# 1-Schematic_Dot_PCB_-_Dash.net
KiCad netlist of a schematic drawn in EasyEDA
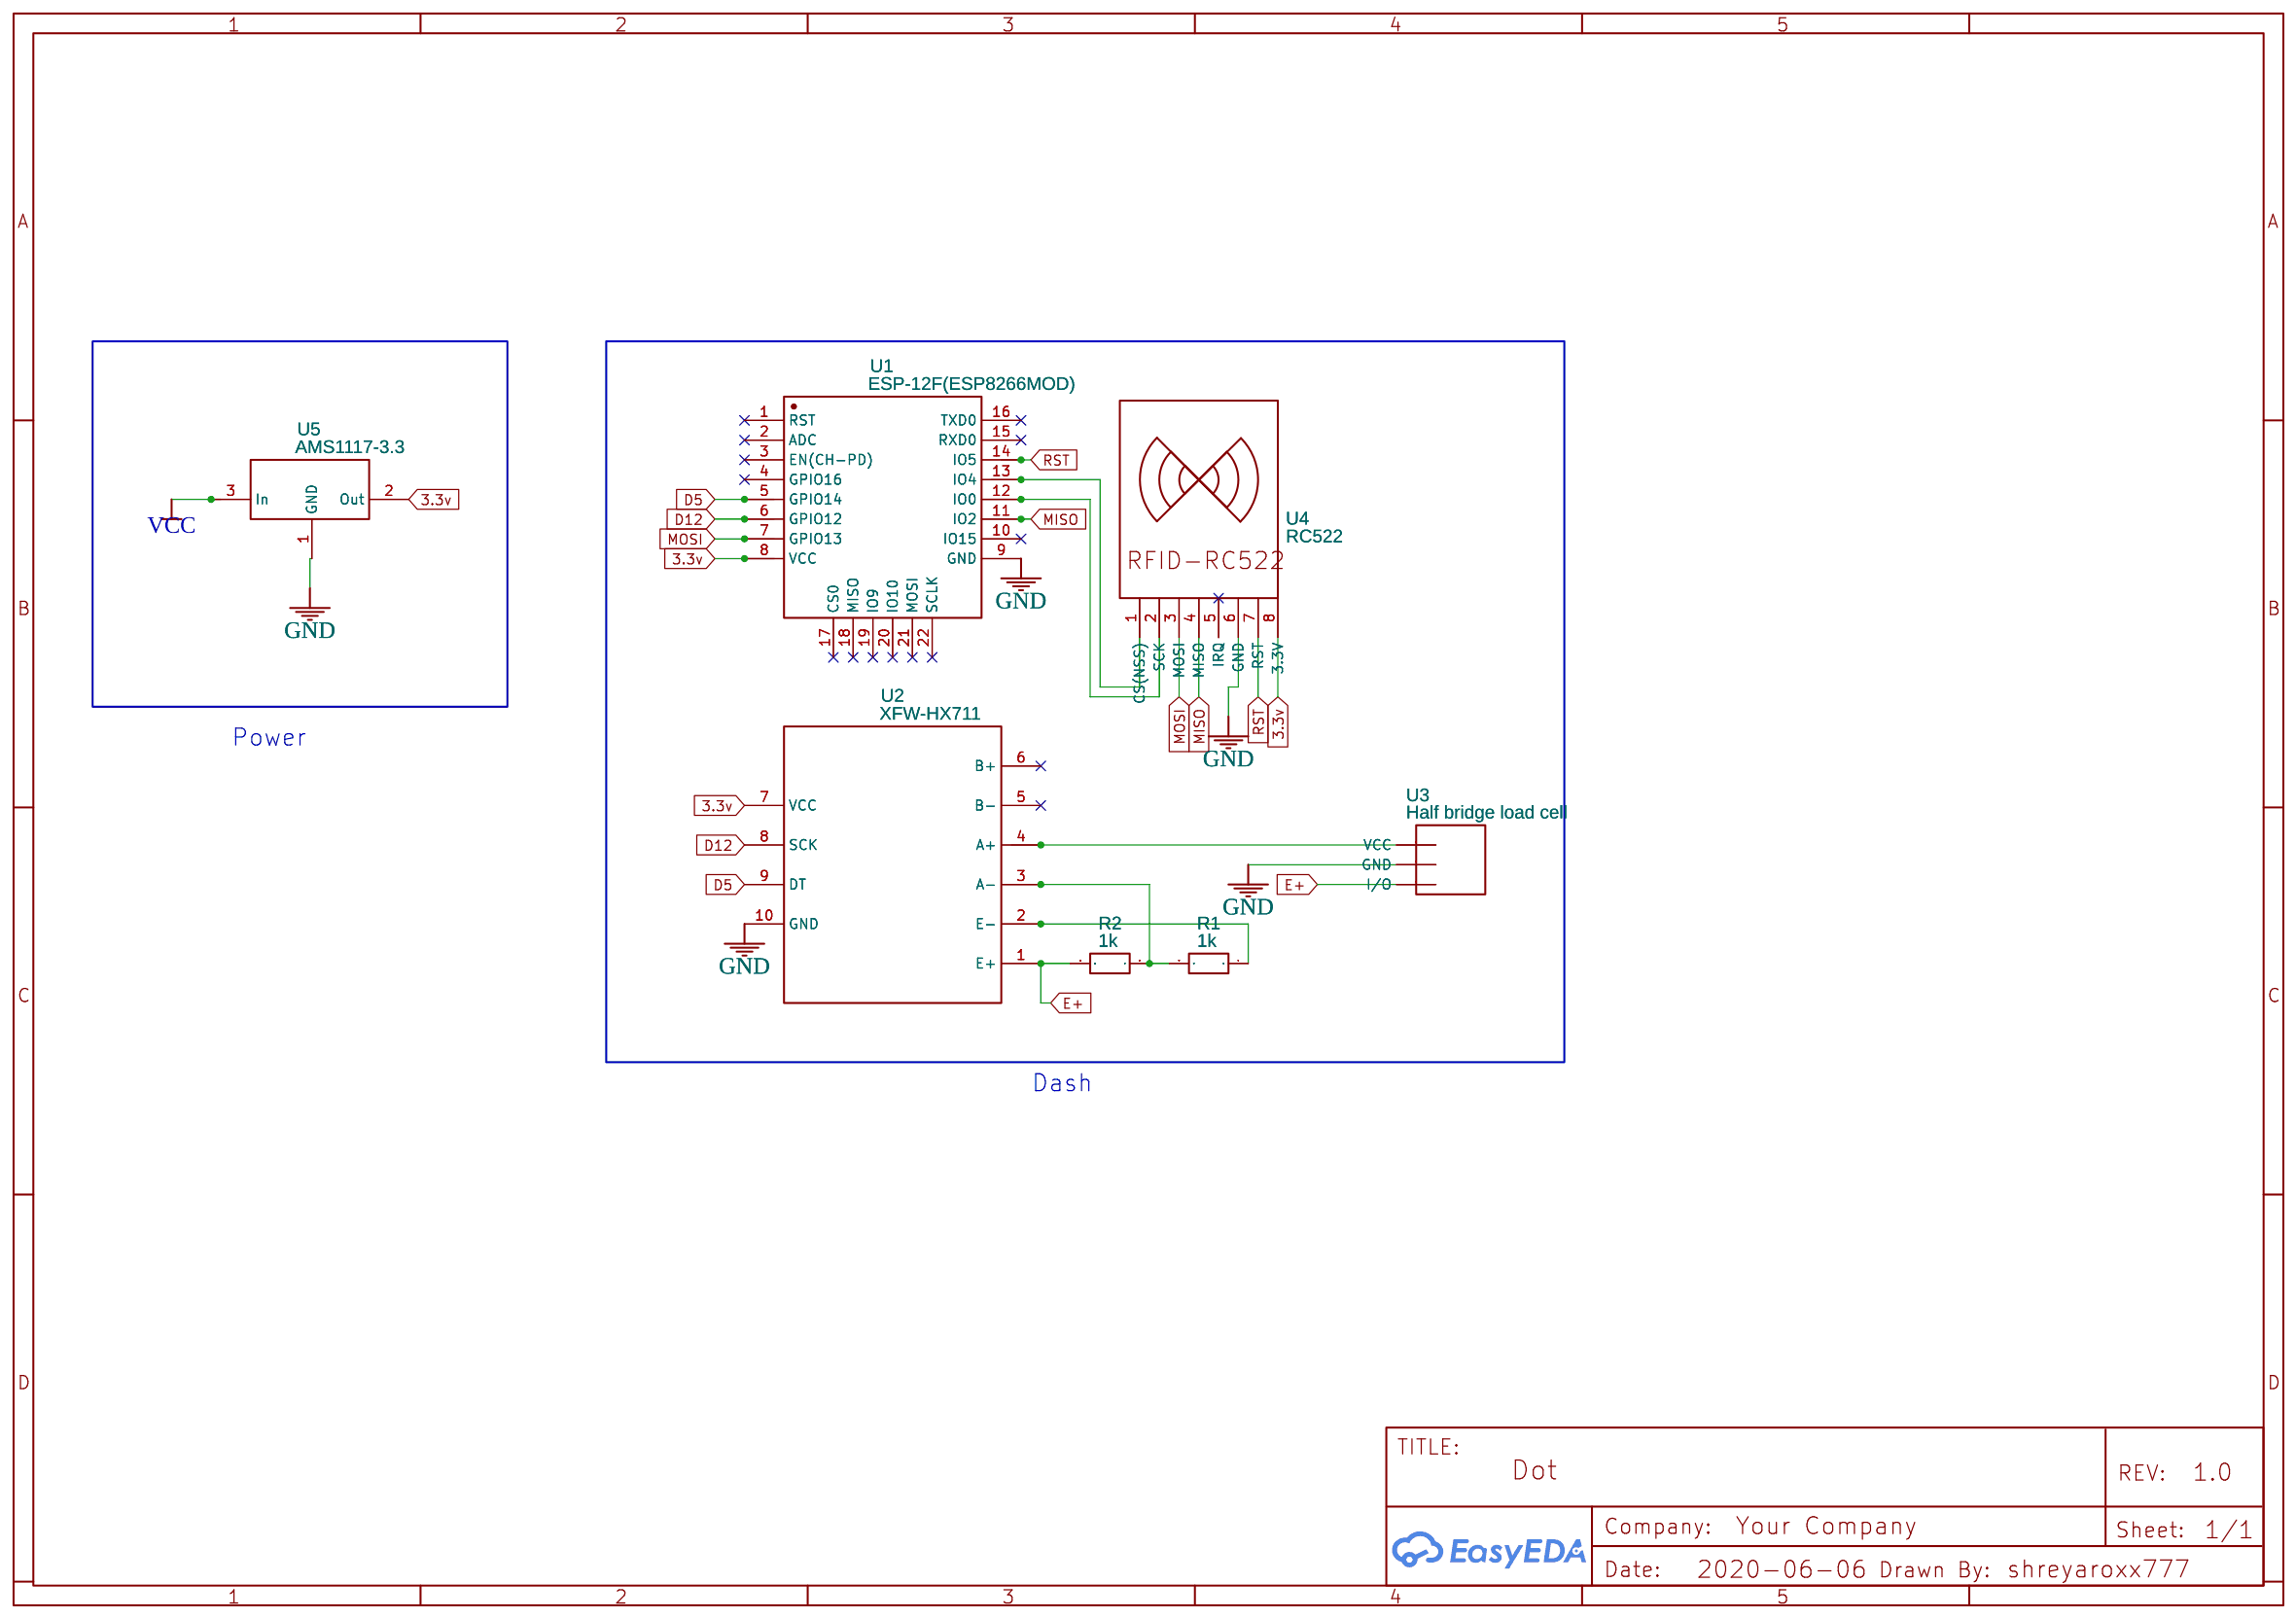
[diagram p0: schematic sheet]

(export (version "E")
  (design (tool "Eeschema 10.0.6"))
  (components
    (comp (ref "R1") (value "1k") (libsource (lib "") (part "R_0201_EU")))
    (comp (ref "R2") (value "1k") (libsource (lib "") (part "R_0201_EU")))
    (comp (ref "U1")
      (value "ESP-12F(ESP8266MOD)")
      (fields (field (name "BOM_Supplier Part") "C82891"))
      (libsource (lib "") (part "ESP-12F(ESP8266MOD)"))
    )
    (comp (ref "U2") (value "XFW-HX711") (libsource (lib "") (part "XFW-HX711")))
    (comp (ref "U3") (value "Half bridge load cell") (libsource (lib "") (part "Half bridge load cell")))
    (comp (ref "U4") (value "RC522") (libsource (lib "") (part "RC522")))
    (comp (ref "U5")
      (value "AMS1117-3.3")
      (fields (field (name "BOM_Supplier Part") "C6186"))
      (libsource (lib "") (part "AMS1117-3.3"))
    )
  )
  (nets
    (net (code "1") (name "3.3v") (class "Default")
      (node (ref "U1") (pin "8") (pinfunction "VCC_8") (pintype "unspecified"))
      (node (ref "U2") (pin "7") (pinfunction "VCC_7") (pintype "unspecified"))
      (node (ref "U4") (pin "8") (pinfunction "3.3V_8") (pintype "unspecified"))
      (node (ref "U5") (pin "2") (pinfunction "Out_2") (pintype "unspecified"))
    )
    (net (code "2") (name "D5") (class "Default")
      (node (ref "U1") (pin "5") (pinfunction "GPIO14_5") (pintype "unspecified"))
      (node (ref "U2") (pin "9") (pinfunction "DT_9") (pintype "unspecified"))
    )
    (net (code "3") (name "D12") (class "Default")
      (node (ref "U1") (pin "6") (pinfunction "GPIO12_6") (pintype "unspecified"))
      (node (ref "U2") (pin "8") (pinfunction "SCK_8") (pintype "unspecified"))
    )
    (net (code "4") (name "E+") (class "Default")
      (node (ref "R2") (pin "2") (pinfunction "2_2") (pintype "unspecified"))
      (node (ref "U2") (pin "1") (pinfunction "E+_1") (pintype "unspecified"))
      (node (ref "U3") (pin "3") (pinfunction "I/O_3") (pintype "unspecified"))
    )
    (net (code "5") (name "GND") (class "Default")
      (node (ref "U1") (pin "9") (pinfunction "GND_9") (pintype "unspecified"))
      (node (ref "U2") (pin "10") (pinfunction "GND_10") (pintype "unspecified"))
      (node (ref "U3") (pin "2") (pinfunction "GND_2") (pintype "unspecified"))
      (node (ref "U4") (pin "6") (pinfunction "GND_6") (pintype "unspecified"))
      (node (ref "U5") (pin "1") (pinfunction "GND_1") (pintype "unspecified"))
    )
    (net (code "6") (name "MISO") (class "Default")
      (node (ref "U1") (pin "11") (pinfunction "IO2_11") (pintype "unspecified"))
      (node (ref "U4") (pin "4") (pinfunction "MISO_4") (pintype "unspecified"))
    )
    (net (code "7") (name "MOSI") (class "Default")
      (node (ref "U1") (pin "7") (pinfunction "GPIO13_7") (pintype "unspecified"))
      (node (ref "U4") (pin "3") (pinfunction "MOSI_3") (pintype "unspecified"))
    )
    (net (code "8") (name "Net-(U1-IO0)") (class "Default")
      (node (ref "U1") (pin "12") (pinfunction "IO0_12") (pintype "unspecified"))
      (node (ref "U4") (pin "2") (pinfunction "SCK_2") (pintype "unspecified"))
    )
    (net (code "9") (name "Net-(U1-IO4)") (class "Default")
      (node (ref "U1") (pin "13") (pinfunction "IO4_13") (pintype "unspecified"))
      (node (ref "U4") (pin "1") (pinfunction "CS(NSS)_1") (pintype "unspecified"))
    )
    (net (code "10") (name "Net-(U2-A+)") (class "Default")
      (node (ref "U2") (pin "4") (pinfunction "A+_4") (pintype "unspecified"))
      (node (ref "U3") (pin "1") (pinfunction "VCC_1") (pintype "unspecified"))
    )
    (net (code "11") (name "Net-(U2-A-)") (class "Default")
      (node (ref "R1") (pin "2") (pinfunction "2_2") (pintype "unspecified"))
      (node (ref "R2") (pin "1") (pinfunction "1_1") (pintype "unspecified"))
      (node (ref "U2") (pin "3") (pinfunction "A-_3") (pintype "unspecified"))
    )
    (net (code "12") (name "Net-(U2-E-)") (class "Default")
      (node (ref "R1") (pin "1") (pinfunction "1_1") (pintype "unspecified"))
      (node (ref "U2") (pin "2") (pinfunction "E-_2") (pintype "unspecified"))
    )
    (net (code "13") (name "RST") (class "Default")
      (node (ref "U1") (pin "14") (pinfunction "IO5_14") (pintype "unspecified"))
      (node (ref "U4") (pin "7") (pinfunction "RST_7") (pintype "unspecified"))
    )
    (net (code "14") (name "VCC") (class "Default")
      (node (ref "U5") (pin "3") (pinfunction "In_3") (pintype "unspecified"))
    )
    (net (code "15") (name "unconnected-(U1-ADC-Pad2)") (class "Default")
      (node (ref "U1") (pin "2") (pinfunction "ADC_2") (pintype "unspecified+no_connect"))
    )
    (net (code "16") (name "unconnected-(U1-CS0-Pad17)") (class "Default")
      (node (ref "U1") (pin "17") (pinfunction "CS0_17") (pintype "unspecified+no_connect"))
    )
    (net (code "17") (name "unconnected-(U1-EN(CH-PD)-Pad3)") (class "Default")
      (node (ref "U1") (pin "3") (pinfunction "EN(CH-PD)_3") (pintype "unspecified+no_connect"))
    )
    (net (code "18") (name "unconnected-(U1-GPIO16-Pad4)") (class "Default")
      (node (ref "U1") (pin "4") (pinfunction "GPIO16_4") (pintype "unspecified+no_connect"))
    )
    (net (code "19") (name "unconnected-(U1-IO9-Pad19)") (class "Default")
      (node (ref "U1") (pin "19") (pinfunction "IO9_19") (pintype "unspecified+no_connect"))
    )
    (net (code "20") (name "unconnected-(U1-IO10-Pad20)") (class "Default")
      (node (ref "U1") (pin "20") (pinfunction "IO10_20") (pintype "unspecified+no_connect"))
    )
    (net (code "21") (name "unconnected-(U1-IO15-Pad10)") (class "Default")
      (node (ref "U1") (pin "10") (pinfunction "IO15_10") (pintype "unspecified+no_connect"))
    )
    (net (code "22") (name "unconnected-(U1-MISO-Pad18)") (class "Default")
      (node (ref "U1") (pin "18") (pinfunction "MISO_18") (pintype "unspecified+no_connect"))
    )
    (net (code "23") (name "unconnected-(U1-MOSI-Pad21)") (class "Default")
      (node (ref "U1") (pin "21") (pinfunction "MOSI_21") (pintype "unspecified+no_connect"))
    )
    (net (code "24") (name "unconnected-(U1-RST-Pad1)") (class "Default")
      (node (ref "U1") (pin "1") (pinfunction "RST_1") (pintype "unspecified+no_connect"))
    )
    (net (code "25") (name "unconnected-(U1-RXD0-Pad15)") (class "Default")
      (node (ref "U1") (pin "15") (pinfunction "RXD0_15") (pintype "unspecified+no_connect"))
    )
    (net (code "26") (name "unconnected-(U1-SCLK-Pad22)") (class "Default")
      (node (ref "U1") (pin "22") (pinfunction "SCLK_22") (pintype "unspecified+no_connect"))
    )
    (net (code "27") (name "unconnected-(U1-TXD0-Pad16)") (class "Default")
      (node (ref "U1") (pin "16") (pinfunction "TXD0_16") (pintype "unspecified+no_connect"))
    )
    (net (code "28") (name "unconnected-(U2-B+-Pad6)") (class "Default")
      (node (ref "U2") (pin "6") (pinfunction "B+_6") (pintype "unspecified+no_connect"))
    )
    (net (code "29") (name "unconnected-(U2-B--Pad5)") (class "Default")
      (node (ref "U2") (pin "5") (pinfunction "B-_5") (pintype "unspecified+no_connect"))
    )
    (net (code "30") (name "unconnected-(U4-IRQ-Pad5)") (class "Default")
      (node (ref "U4") (pin "5") (pinfunction "IRQ_5") (pintype "unspecified+no_connect"))
    )
  )
)
